# MOD-SH-RFDET-01.net
KiCad netlist of a schematic drawn in Altium Designer
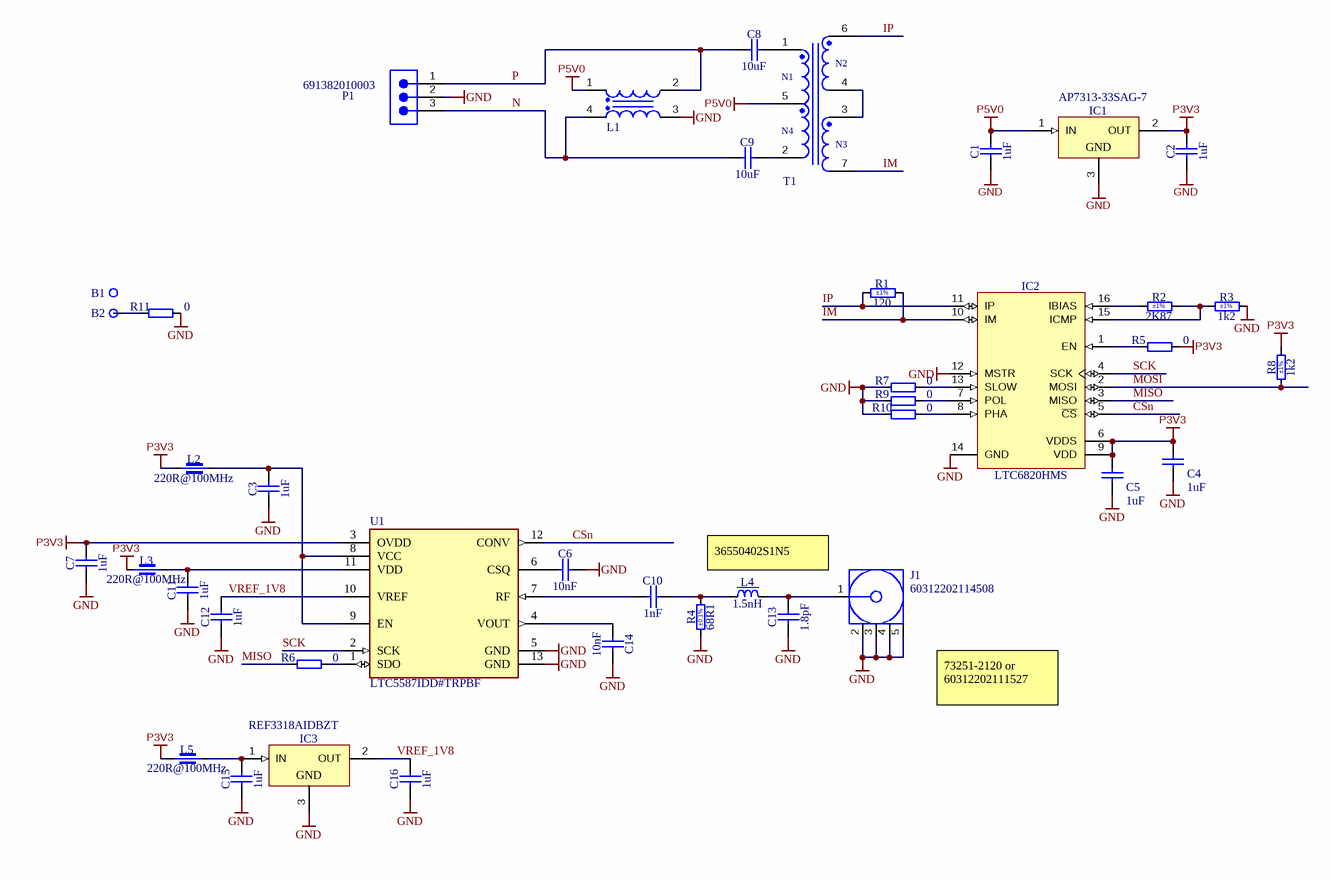
[diagram p0: MOD-SH-RFDET-01.SchDoc]

(export (version "E")
  (design (tool "Eeschema 10.0.6"))
  (components
    (comp (ref "B1")
      (value "Plated Hole")
      (footprint "MTG320_550")
      (description "Single Terminal Socket")
      (fields (field (name "PART NUMBER") "PLATED_HOLE3.2_PAD5.5") (field (name "AUTHOR") "CERN DEM JMW"))
      (libsource (lib "Eletro-mechanical") (part "Single Terminal Socket"))
    )
    (comp (ref "B2")
      (value "Plated Hole")
      (footprint "MTG320_550")
      (description "Single Terminal Socket")
      (fields (field (name "PART NUMBER") "PLATED_HOLE3.2_PAD5.5") (field (name "AUTHOR") "CERN DEM JMW"))
      (libsource (lib "Eletro-mechanical") (part "Single Terminal Socket"))
    )
    (comp (ref "C1")
      (value "1uF")
      (footprint "CAPC1005X55N")
      (description "Non-polarised capacitor")
      (fields
        (field (name "PART NUMBER") "CC0402_1UF_16V_10%_X5R")
        (field (name "VOLTAGE") "16V")
        (field (name "AUTHOR") "CERN DEM JLC")
      )
      (libsource (lib "Capacitors") (part "Capacitor - non polarized"))
    )
    (comp (ref "C2")
      (value "1uF")
      (footprint "CAPC1005X55N")
      (description "Non-polarised capacitor")
      (fields
        (field (name "PART NUMBER") "CC0402_1UF_16V_10%_X5R")
        (field (name "VOLTAGE") "16V")
        (field (name "AUTHOR") "CERN DEM JLC")
      )
      (libsource (lib "Capacitors") (part "Capacitor - non polarized"))
    )
    (comp (ref "C3")
      (value "1uF")
      (footprint "CAPC1005X55N")
      (description "Non-polarised capacitor")
      (fields
        (field (name "PART NUMBER") "CC0402_1UF_16V_10%_X5R")
        (field (name "VOLTAGE") "16V")
        (field (name "AUTHOR") "CERN DEM JLC")
      )
      (libsource (lib "Capacitors") (part "Capacitor - non polarized"))
    )
    (comp (ref "C4")
      (value "1uF")
      (footprint "CAPC1005X55N")
      (description "Non-polarised capacitor")
      (fields
        (field (name "PART NUMBER") "CC0402_1UF_16V_10%_X5R")
        (field (name "VOLTAGE") "16V")
        (field (name "AUTHOR") "CERN DEM JLC")
      )
      (libsource (lib "Capacitors") (part "Capacitor - non polarized"))
    )
    (comp (ref "C5")
      (value "1uF")
      (footprint "CAPC1005X55N")
      (description "Non-polarised capacitor")
      (fields
        (field (name "PART NUMBER") "CC0402_1UF_16V_10%_X5R")
        (field (name "VOLTAGE") "16V")
        (field (name "AUTHOR") "CERN DEM JLC")
      )
      (libsource (lib "Capacitors") (part "Capacitor - non polarized"))
    )
    (comp (ref "C6")
      (value "10nF")
      (footprint "CAPC1608X87N")
      (description "Non-polarised capacitor")
      (fields
        (field (name "PART NUMBER") "CC0603_10NF_50V_5%_C0G")
        (field (name "VOLTAGE") "50V")
        (field (name "AUTHOR") "CERN DEM JLC")
      )
      (libsource (lib "Capacitors") (part "Capacitor - non polarized"))
    )
    (comp (ref "C7")
      (value "1uF")
      (footprint "CAPC1005X55N")
      (description "Non-polarised capacitor")
      (fields
        (field (name "PART NUMBER") "CC0402_1UF_16V_10%_X5R")
        (field (name "VOLTAGE") "16V")
        (field (name "AUTHOR") "CERN DEM JLC")
      )
      (libsource (lib "Capacitors") (part "Capacitor - non polarized"))
    )
    (comp (ref "C8")
      (value "10uF")
      (footprint "CAPC1608X80N")
      (description "Non-polarised capacitor")
      (fields
        (field (name "PART NUMBER") "CC0603_10UF_16V_20%_X5R")
        (field (name "VOLTAGE") "16V")
        (field (name "AUTHOR") "CERN DEM MR")
      )
      (libsource (lib "Capacitors") (part "Capacitor - non polarized"))
    )
    (comp (ref "C9")
      (value "10uF")
      (footprint "CAPC1608X80N")
      (description "Non-polarised capacitor")
      (fields
        (field (name "PART NUMBER") "CC0603_10UF_16V_20%_X5R")
        (field (name "VOLTAGE") "16V")
        (field (name "AUTHOR") "CERN DEM MR")
      )
      (libsource (lib "Capacitors") (part "Capacitor - non polarized"))
    )
    (comp (ref "C10")
      (value "1nF")
      (footprint "CAPC1005X55N")
      (description "Non-polarised capacitor")
      (fields
        (field (name "PART NUMBER") "CC0402_1NF_50V_10%_X7R")
        (field (name "VOLTAGE") "50V")
        (field (name "AUTHOR") "CERN DEM JLC")
      )
      (libsource (lib "Capacitors") (part "Capacitor - non polarized"))
    )
    (comp (ref "C11")
      (value "1uF")
      (footprint "CAPC1005X55N")
      (description "Non-polarised capacitor")
      (fields
        (field (name "PART NUMBER") "CC0402_1UF_16V_10%_X5R")
        (field (name "VOLTAGE") "16V")
        (field (name "AUTHOR") "CERN DEM JLC")
      )
      (libsource (lib "Capacitors") (part "Capacitor - non polarized"))
    )
    (comp (ref "C12")
      (value "1uF")
      (footprint "CAPC1005X55N")
      (description "Non-polarised capacitor")
      (fields
        (field (name "PART NUMBER") "CC0402_1UF_16V_10%_X5R")
        (field (name "VOLTAGE") "16V")
        (field (name "AUTHOR") "CERN DEM JLC")
      )
      (libsource (lib "Capacitors") (part "Capacitor - non polarized"))
    )
    (comp (ref "C13")
      (value "1.8pF")
      (footprint "CAPC1005X55N")
      (description "Non-polarised capacitor")
      (fields
        (field (name "PART NUMBER") "CC0402_1.8PF_50V_0.25PF_C0G")
        (field (name "VOLTAGE") "50V")
        (field (name "AUTHOR") "CERN DEM JLC")
      )
      (libsource (lib "Capacitors") (part "Capacitor - non polarized"))
    )
    (comp (ref "C14")
      (value "10nF")
      (footprint "CAPC1608X87N")
      (description "Non-polarised capacitor")
      (fields
        (field (name "PART NUMBER") "CC0603_10NF_50V_5%_C0G")
        (field (name "VOLTAGE") "50V")
        (field (name "AUTHOR") "CERN DEM JLC")
      )
      (libsource (lib "Capacitors") (part "Capacitor - non polarized"))
    )
    (comp (ref "C15")
      (value "1uF")
      (footprint "CAPC1005X55N")
      (description "Non-polarised capacitor")
      (fields
        (field (name "PART NUMBER") "CC0402_1UF_16V_10%_X5R")
        (field (name "VOLTAGE") "16V")
        (field (name "AUTHOR") "CERN DEM JLC")
      )
      (libsource (lib "Capacitors") (part "Capacitor - non polarized"))
    )
    (comp (ref "C16")
      (value "1uF")
      (footprint "CAPC1005X55N")
      (description "Non-polarised capacitor")
      (fields
        (field (name "PART NUMBER") "CC0402_1UF_16V_10%_X5R")
        (field (name "VOLTAGE") "16V")
        (field (name "AUTHOR") "CERN DEM JLC")
      )
      (libsource (lib "Capacitors") (part "Capacitor - non polarized"))
    )
    (comp (ref "IC1")
      (value "AP7313-33SAG-7")
      (footprint "SOT95P240X130-3N")
      (description "3-Terminal Regulator 1=IN 2=OUT 3=GND")
      (fields (field (name "MANUFACTURER") "DIODES INCORPORATED") (field (name "AUTHOR") "CERN DEM JLC"))
      (libsource (lib "ICs And Semiconductors") (part "REG3 1IN-2OUT-3GND"))
    )
    (comp (ref "IC2")
      (value "LTC6820HMS")
      (footprint "SOP50P490X110-16N")
      (description "isoSPI Isolated Communications Interface")
      (fields (field (name "MANUFACTURER") "ANALOG DEVICES") (field (name "AUTHOR") "CERN DEM BC"))
      (libsource (lib "ICs And Semiconductors") (part "LTC6820xMS"))
    )
    (comp (ref "IC3")
      (value "REF3318AIDBZT")
      (footprint "SOT95P237X112-3N")
      (description "3-Terminal Regulator 1=IN 2=OUT 3=GND")
      (fields (field (name "MANUFACTURER") "TEXAS INSTRUMENTS") (field (name "AUTHOR") "CERN DEM JLC"))
      (libsource (lib "ICs And Semiconductors") (part "REG3 1IN-2OUT-3GND"))
    )
    (comp (ref "J1")
      (value "60312202114508")
      (footprint "60312202114508")
      (description "WR-SMA Connector, PCB End Launch Jack, 6.35SQ Flange Round Post for PCB 1.1mm, DC~18GHz, 50Ω")
      (fields (field (name "MANUFACTURER") "Wurth Elektronik"))
      (libsource (lib "Altium_WR-SMA (rev25a)") (part "60312202114508"))
    )
    (comp (ref "L1")
      (value "100µH, 0.3A")
      (footprint "WE-DD_7332")
      (description "WE-DD SMT Shielded Coupled Inductor, size 7332, 100µH, 0.3A, 1730mΩ")
      (fields
        (field (name "MANUFACTURER PART NUMBER") "744878101")
        (field (name "MANUFACTURER") "Wurth Elektronik")
      )
      (libsource (lib "WE-DD (rev22b)") (part "744878101"))
    )
    (comp (ref "L2")
      (value "220R@100MHz")
      (footprint "INDC1608X95N")
      (fields
        (field (name "PART NUMBER") "IND0603_MURATA_BLM18SG221TN1")
        (field (name "POWER") "2.5A")
        (field (name "TOLERANCE") "±25%")
        (field (name "AUTHOR") "CERN DEM MR")
      )
      (libsource (lib "Inductors & Transformers") (part "Ferrite Bead"))
    )
    (comp (ref "L3")
      (value "220R@100MHz")
      (footprint "INDC1608X95N")
      (fields
        (field (name "PART NUMBER") "IND0603_MURATA_BLM18SG221TN1")
        (field (name "POWER") "2.5A")
        (field (name "TOLERANCE") "±25%")
        (field (name "AUTHOR") "CERN DEM MR")
      )
      (libsource (lib "Inductors & Transformers") (part "Ferrite Bead"))
    )
    (comp (ref "L4")
      (value "1.5nH")
      (footprint "IND_MURATA_LQP15MN_02")
      (description "Inductor With Core")
      (fields
        (field (name "PART NUMBER") "IND0402_1.5NH_0.1NH_MURATA_LQP15MN1N5B02")
        (field (name "POWER") "280mA")
        (field (name "AUTHOR") "CERN DEM BC")
      )
      (libsource (lib "Inductors & Transformers") (part "Inductor With Magnetic core"))
    )
    (comp (ref "L5")
      (value "220R@100MHz")
      (footprint "INDC1608X95N")
      (fields
        (field (name "PART NUMBER") "IND0603_MURATA_BLM18SG221TN1")
        (field (name "POWER") "2.5A")
        (field (name "TOLERANCE") "±25%")
        (field (name "AUTHOR") "CERN DEM MR")
      )
      (libsource (lib "Inductors & Transformers") (part "Ferrite Bead"))
    )
    (comp (ref "P1")
      (value "691382010003")
      (footprint "691382010003")
      (description "WR-TBL Series 382 Horizontal PCB Header, THT, pitch 2.5mm, 03p")
      (fields (field (name "MANUFACTURER") "Wurth Elektronik"))
      (libsource (lib "Altium_WR-TBL_Pluggable Connector (rev25b)") (part "691382010003"))
    )
    (comp (ref "R1")
      (value "120")
      (footprint "RESC1608X55N")
      (description "Resistor - 1%")
      (fields
        (field (name "TOLERANCE") "±1%")
        (field (name "PART NUMBER") "R0603_120R_1%_0.1W_100PPM")
        (field (name "POWER") "0.1W")
        (field (name "AUTHOR") "CERN DEM JLC")
      )
      (libsource (lib "Resistors") (part "Resistor - 1%"))
    )
    (comp (ref "R2")
      (value "2K87")
      (footprint "RESC1005X40N")
      (description "Resistor - 1%")
      (fields
        (field (name "TOLERANCE") "±1%")
        (field (name "PART NUMBER") "R0402_2K87_1%_0.063W_100PPM")
        (field (name "POWER") "0.063W")
        (field (name "AUTHOR") "CERN DEM BC")
      )
      (libsource (lib "Resistors") (part "Resistor - 1%"))
    )
    (comp (ref "R3")
      (value "1k2")
      (footprint "RESC1005X40N")
      (description "Resistor - 1%")
      (fields
        (field (name "TOLERANCE") "±1%")
        (field (name "PART NUMBER") "R0402_1K2_1%_0.0625W_100PPM")
        (field (name "POWER") "0.0625W")
        (field (name "AUTHOR") "CERN DEM JLC")
      )
      (libsource (lib "Resistors") (part "Resistor - 1%"))
    )
    (comp (ref "R4")
      (value "68R1")
      (footprint "RESC2012X60N")
      (description "Resistor - 0.1%")
      (fields
        (field (name "TOLERANCE") "±0.1%")
        (field (name "PART NUMBER") "R0805_68R1_0.1%_0.1W_10PPM")
        (field (name "POWER") "0.1W")
        (field (name "AUTHOR") "CERN DEM JLC")
      )
      (libsource (lib "Resistors") (part "Resistor - 0.1%"))
    )
    (comp (ref "R5")
      (value "0")
      (footprint "RESC1005X40N")
      (description "Resistor")
      (fields
        (field (name "PART NUMBER") "R0402_0R_JUMPER")
        (field (name "MANUFACTURER") "GENERIC")
        (field (name "AUTHOR") "CERN DEM JLC")
      )
      (libsource (lib "Resistors") (part "Resistor"))
    )
    (comp (ref "R6")
      (value "0")
      (footprint "RESC1005X40N")
      (description "Resistor")
      (fields
        (field (name "PART NUMBER") "R0402_0R_JUMPER")
        (field (name "MANUFACTURER") "GENERIC")
        (field (name "AUTHOR") "CERN DEM JLC")
      )
      (libsource (lib "Resistors") (part "Resistor"))
    )
    (comp (ref "R7")
      (value "0")
      (footprint "RESC1005X40N")
      (description "Resistor")
      (fields
        (field (name "PART NUMBER") "R0402_0R_JUMPER")
        (field (name "MANUFACTURER") "GENERIC")
        (field (name "AUTHOR") "CERN DEM JLC")
      )
      (libsource (lib "Resistors") (part "Resistor"))
    )
    (comp (ref "R8")
      (value "1k2")
      (footprint "RESC1005X40N")
      (description "Resistor - 1%")
      (fields
        (field (name "TOLERANCE") "±1%")
        (field (name "PART NUMBER") "R0402_1K2_1%_0.0625W_100PPM")
        (field (name "POWER") "0.0625W")
        (field (name "AUTHOR") "CERN DEM JLC")
      )
      (libsource (lib "Resistors") (part "Resistor - 1%"))
    )
    (comp (ref "R9")
      (value "0")
      (footprint "RESC1005X40N")
      (description "Resistor")
      (fields
        (field (name "PART NUMBER") "R0402_0R_JUMPER")
        (field (name "MANUFACTURER") "GENERIC")
        (field (name "AUTHOR") "CERN DEM JLC")
      )
      (libsource (lib "Resistors") (part "Resistor"))
    )
    (comp (ref "R10")
      (value "0")
      (footprint "RESC1005X40N")
      (description "Resistor")
      (fields
        (field (name "PART NUMBER") "R0402_0R_JUMPER")
        (field (name "MANUFACTURER") "GENERIC")
        (field (name "AUTHOR") "CERN DEM JLC")
      )
      (libsource (lib "Resistors") (part "Resistor"))
    )
    (comp (ref "R11")
      (value "0")
      (footprint "RESC1005X40N")
      (description "Resistor")
      (fields
        (field (name "PART NUMBER") "R0402_0R_JUMPER")
        (field (name "MANUFACTURER") "GENERIC")
        (field (name "AUTHOR") "CERN DEM JLC")
      )
      (libsource (lib "Resistors") (part "Resistor"))
    )
    (comp (ref "T1")
      (value "74930030")
      (footprint "74930030")
      (description "WE-STST SMT Super Tiny Signal Transformer, size 4532, 1:1, 350uH")
      (fields (field (name "MANUFACTURER") "Wurth Elektronik"))
      (libsource (lib "Altium_WE-STST (rev24a)") (part "74930030"))
    )
    (comp (ref "U1")
      (value "LTC5587IDD#TRPBF")
      (footprint "FP-DD-12-05-08-1725-IPC_A")
      (description "IC RF DETECT 10MHZ-6GHZ 12DFN")
      (libsource (lib "Altium Content Vault") (part "e4a5e3ae19514cf54a31bd6a68b987f"))
    )
  )
  (nets
    (net (code "1") (name "/CSn") (class "Default")
      (node (ref "IC2") (pin "5") (pinfunction "~{CS}_5") (pintype "bidirectional"))
      (node (ref "U1") (pin "12") (pinfunction "CONV_12") (pintype "output"))
    )
    (net (code "2") (name "/IM") (class "Default")
      (node (ref "IC2") (pin "10") (pinfunction "IM_10") (pintype "bidirectional"))
      (node (ref "R1") (pin "2") (pinfunction "2_2") (pintype "passive"))
      (node (ref "T1") (pin "7") (pinfunction "7_7") (pintype "passive"))
    )
    (net (code "3") (name "/IP") (class "Default")
      (node (ref "IC2") (pin "11") (pinfunction "IP_11") (pintype "bidirectional"))
      (node (ref "R1") (pin "1") (pinfunction "1_1") (pintype "passive"))
      (node (ref "T1") (pin "6") (pinfunction "6_6") (pintype "passive"))
    )
    (net (code "4") (name "/MISO") (class "Default")
      (node (ref "IC2") (pin "3") (pinfunction "MISO_3") (pintype "bidirectional"))
      (node (ref "R6") (pin "1") (pinfunction "1_1") (pintype "passive"))
    )
    (net (code "5") (name "/MOSI") (class "Default")
      (node (ref "IC2") (pin "2") (pinfunction "MOSI_2") (pintype "bidirectional"))
      (node (ref "R8") (pin "1") (pinfunction "1_1") (pintype "passive"))
    )
    (net (code "6") (name "/N") (class "Default")
      (node (ref "C9") (pin "1") (pinfunction "1_1") (pintype "passive"))
      (node (ref "L1") (pin "4") (pinfunction "4_4") (pintype "passive"))
      (node (ref "P1") (pin "3") (pinfunction "3_3") (pintype "passive"))
    )
    (net (code "7") (name "/P") (class "Default")
      (node (ref "C8") (pin "1") (pinfunction "1_1") (pintype "passive"))
      (node (ref "L1") (pin "2") (pinfunction "2_2") (pintype "passive"))
      (node (ref "P1") (pin "1") (pinfunction "1_1") (pintype "passive"))
    )
    (net (code "8") (name "/SCK") (class "Default")
      (node (ref "IC2") (pin "4") (pinfunction "SCK_4") (pintype "bidirectional"))
      (node (ref "U1") (pin "2") (pinfunction "SCK_2") (pintype "input"))
    )
    (net (code "9") (name "/VREF_1V8") (class "Default")
      (node (ref "C12") (pin "2") (pinfunction "2_2") (pintype "passive"))
      (node (ref "C16") (pin "2") (pinfunction "2_2") (pintype "passive"))
      (node (ref "IC3") (pin "2") (pinfunction "OUT_2") (pintype "power_in"))
      (node (ref "U1") (pin "10") (pinfunction "VREF_10") (pintype "power_in"))
    )
    (net (code "10") (name "GND") (class "Default")
      (node (ref "C1") (pin "1") (pinfunction "1_1") (pintype "passive"))
      (node (ref "C11") (pin "1") (pinfunction "1_1") (pintype "passive"))
      (node (ref "C12") (pin "1") (pinfunction "1_1") (pintype "passive"))
      (node (ref "C13") (pin "1") (pinfunction "1_1") (pintype "passive"))
      (node (ref "C14") (pin "2") (pinfunction "2_2") (pintype "passive"))
      (node (ref "C15") (pin "1") (pinfunction "1_1") (pintype "passive"))
      (node (ref "C16") (pin "1") (pinfunction "1_1") (pintype "passive"))
      (node (ref "C2") (pin "1") (pinfunction "1_1") (pintype "passive"))
      (node (ref "C3") (pin "1") (pinfunction "1_1") (pintype "passive"))
      (node (ref "C4") (pin "1") (pinfunction "1_1") (pintype "passive"))
      (node (ref "C5") (pin "1") (pinfunction "1_1") (pintype "passive"))
      (node (ref "C6") (pin "2") (pinfunction "2_2") (pintype "passive"))
      (node (ref "C7") (pin "1") (pinfunction "1_1") (pintype "passive"))
      (node (ref "IC1") (pin "3") (pinfunction "GND_3") (pintype "power_in"))
      (node (ref "IC2") (pin "12") (pinfunction "MSTR_12") (pintype "input"))
      (node (ref "IC2") (pin "14") (pinfunction "GND_14") (pintype "power_in"))
      (node (ref "IC3") (pin "3") (pinfunction "GND_3") (pintype "power_in"))
      (node (ref "J1") (pin "2") (pinfunction "GND_2") (pintype "passive"))
      (node (ref "J1") (pin "3") (pinfunction "GND_3") (pintype "passive"))
      (node (ref "J1") (pin "4") (pinfunction "GND_4") (pintype "passive"))
      (node (ref "J1") (pin "5") (pinfunction "GND_5") (pintype "passive"))
      (node (ref "L1") (pin "3") (pinfunction "3_3") (pintype "passive"))
      (node (ref "P1") (pin "2") (pinfunction "2_2") (pintype "passive"))
      (node (ref "R10") (pin "1") (pinfunction "1_1") (pintype "passive"))
      (node (ref "R11") (pin "2") (pinfunction "2_2") (pintype "passive"))
      (node (ref "R3") (pin "2") (pinfunction "2_2") (pintype "passive"))
      (node (ref "R4") (pin "1") (pinfunction "1_1") (pintype "passive"))
      (node (ref "R7") (pin "1") (pinfunction "1_1") (pintype "passive"))
      (node (ref "R9") (pin "1") (pinfunction "1_1") (pintype "passive"))
      (node (ref "U1") (pin "13") (pinfunction "GND_13") (pintype "power_in"))
      (node (ref "U1") (pin "5") (pinfunction "GND_5") (pintype "power_in"))
    )
    (net (code "11") (name "Net-(B2-Pad1)") (class "Default")
      (node (ref "B2") (pin "1") (pinfunction "1_1") (pintype "bidirectional"))
      (node (ref "R11") (pin "1") (pinfunction "1_1") (pintype "passive"))
    )
    (net (code "12") (name "Net-(C8-Pad2)") (class "Default")
      (node (ref "C8") (pin "2") (pinfunction "2_2") (pintype "passive"))
      (node (ref "T1") (pin "1") (pinfunction "1_1") (pintype "passive"))
    )
    (net (code "13") (name "Net-(C9-Pad2)") (class "Default")
      (node (ref "C9") (pin "2") (pinfunction "2_2") (pintype "passive"))
      (node (ref "T1") (pin "2") (pinfunction "2_2") (pintype "passive"))
    )
    (net (code "14") (name "Net-(C10-Pad2)") (class "Default")
      (node (ref "C10") (pin "2") (pinfunction "2_2") (pintype "passive"))
      (node (ref "L4") (pin "1") (pinfunction "1_1") (pintype "passive"))
      (node (ref "R4") (pin "2") (pinfunction "2_2") (pintype "passive"))
    )
    (net (code "15") (name "Net-(IC2-EN)") (class "Default")
      (node (ref "IC2") (pin "1") (pinfunction "EN_1") (pintype "input"))
      (node (ref "R5") (pin "1") (pinfunction "1_1") (pintype "passive"))
    )
    (net (code "16") (name "Net-(IC2-IBIAS)") (class "Default")
      (node (ref "IC2") (pin "16") (pinfunction "IBIAS_16") (pintype "input"))
      (node (ref "R2") (pin "1") (pinfunction "1_1") (pintype "passive"))
    )
    (net (code "17") (name "Net-(IC2-ICMP)") (class "Default")
      (node (ref "IC2") (pin "15") (pinfunction "ICMP_15") (pintype "input"))
      (node (ref "R2") (pin "2") (pinfunction "2_2") (pintype "passive"))
      (node (ref "R3") (pin "1") (pinfunction "1_1") (pintype "passive"))
    )
    (net (code "18") (name "Net-(IC2-PHA)") (class "Default")
      (node (ref "IC2") (pin "8") (pinfunction "PHA_8") (pintype "input"))
      (node (ref "R10") (pin "2") (pinfunction "2_2") (pintype "passive"))
    )
    (net (code "19") (name "Net-(IC2-POL)") (class "Default")
      (node (ref "IC2") (pin "7") (pinfunction "POL_7") (pintype "input"))
      (node (ref "R9") (pin "2") (pinfunction "2_2") (pintype "passive"))
    )
    (net (code "20") (name "Net-(IC2-SLOW)") (class "Default")
      (node (ref "IC2") (pin "13") (pinfunction "SLOW_13") (pintype "input"))
      (node (ref "R7") (pin "2") (pinfunction "2_2") (pintype "passive"))
    )
    (net (code "21") (name "Net-(IC3-IN)") (class "Default")
      (node (ref "C15") (pin "2") (pinfunction "2_2") (pintype "passive"))
      (node (ref "IC3") (pin "1") (pinfunction "IN_1") (pintype "input"))
      (node (ref "L5") (pin "2") (pinfunction "2_2") (pintype "passive"))
    )
    (net (code "22") (name "Net-(J1-Signal)") (class "Default")
      (node (ref "C13") (pin "2") (pinfunction "2_2") (pintype "passive"))
      (node (ref "J1") (pin "1") (pinfunction "Signal_1") (pintype "passive"))
      (node (ref "L4") (pin "2") (pinfunction "2_2") (pintype "passive"))
    )
    (net (code "23") (name "Net-(T1-Pad3)") (class "Default")
      (node (ref "T1") (pin "3") (pinfunction "3_3") (pintype "passive"))
      (node (ref "T1") (pin "4") (pinfunction "4_4") (pintype "passive"))
    )
    (net (code "24") (name "Net-(U1-CSQ)") (class "Default")
      (node (ref "C6") (pin "1") (pinfunction "1_1") (pintype "passive"))
      (node (ref "U1") (pin "6") (pinfunction "CSQ_6") (pintype "passive"))
    )
    (net (code "25") (name "Net-(U1-EN)") (class "Default")
      (node (ref "C3") (pin "2") (pinfunction "2_2") (pintype "passive"))
      (node (ref "L2") (pin "2") (pinfunction "2_2") (pintype "passive"))
      (node (ref "U1") (pin "8") (pinfunction "VCC_8") (pintype "power_in"))
      (node (ref "U1") (pin "9") (pinfunction "EN_9") (pintype "passive"))
    )
    (net (code "26") (name "Net-(U1-RF)") (class "Default")
      (node (ref "C10") (pin "1") (pinfunction "1_1") (pintype "passive"))
      (node (ref "U1") (pin "7") (pinfunction "RF_7") (pintype "input"))
    )
    (net (code "27") (name "Net-(U1-SDO)") (class "Default")
      (node (ref "R6") (pin "2") (pinfunction "2_2") (pintype "passive"))
      (node (ref "U1") (pin "1") (pinfunction "SDO_1") (pintype "bidirectional"))
    )
    (net (code "28") (name "Net-(U1-VDD)") (class "Default")
      (node (ref "C11") (pin "2") (pinfunction "2_2") (pintype "passive"))
      (node (ref "L3") (pin "2") (pinfunction "2_2") (pintype "passive"))
      (node (ref "U1") (pin "11") (pinfunction "VDD_11") (pintype "power_in"))
    )
    (net (code "29") (name "Net-(U1-VOUT)") (class "Default")
      (node (ref "C14") (pin "1") (pinfunction "1_1") (pintype "passive"))
      (node (ref "U1") (pin "4") (pinfunction "VOUT_4") (pintype "output"))
    )
    (net (code "30") (name "P3V3") (class "Default")
      (node (ref "C2") (pin "2") (pinfunction "2_2") (pintype "passive"))
      (node (ref "C4") (pin "2") (pinfunction "2_2") (pintype "passive"))
      (node (ref "C5") (pin "2") (pinfunction "2_2") (pintype "passive"))
      (node (ref "C7") (pin "2") (pinfunction "2_2") (pintype "passive"))
      (node (ref "IC1") (pin "2") (pinfunction "OUT_2") (pintype "power_in"))
      (node (ref "IC2") (pin "6") (pinfunction "VDDS_6") (pintype "power_in"))
      (node (ref "IC2") (pin "9") (pinfunction "VDD_9") (pintype "power_in"))
      (node (ref "L2") (pin "1") (pinfunction "1_1") (pintype "passive"))
      (node (ref "L3") (pin "1") (pinfunction "1_1") (pintype "passive"))
      (node (ref "L5") (pin "1") (pinfunction "1_1") (pintype "passive"))
      (node (ref "R5") (pin "2") (pinfunction "2_2") (pintype "passive"))
      (node (ref "R8") (pin "2") (pinfunction "2_2") (pintype "passive"))
      (node (ref "U1") (pin "3") (pinfunction "OVDD_3") (pintype "power_in"))
    )
    (net (code "31") (name "P5V0") (class "Default")
      (node (ref "C1") (pin "2") (pinfunction "2_2") (pintype "passive"))
      (node (ref "IC1") (pin "1") (pinfunction "IN_1") (pintype "input"))
      (node (ref "L1") (pin "1") (pinfunction "1_1") (pintype "passive"))
      (node (ref "T1") (pin "5") (pinfunction "5_5") (pintype "passive"))
    )
    (net (code "32") (name "unconnected-(B1-Pad1)") (class "Default")
      (node (ref "B1") (pin "1") (pinfunction "1_1") (pintype "bidirectional"))
    )
  )
)
